# memorycard.net
KiCad netlist of a schematic drawn in Altium Designer
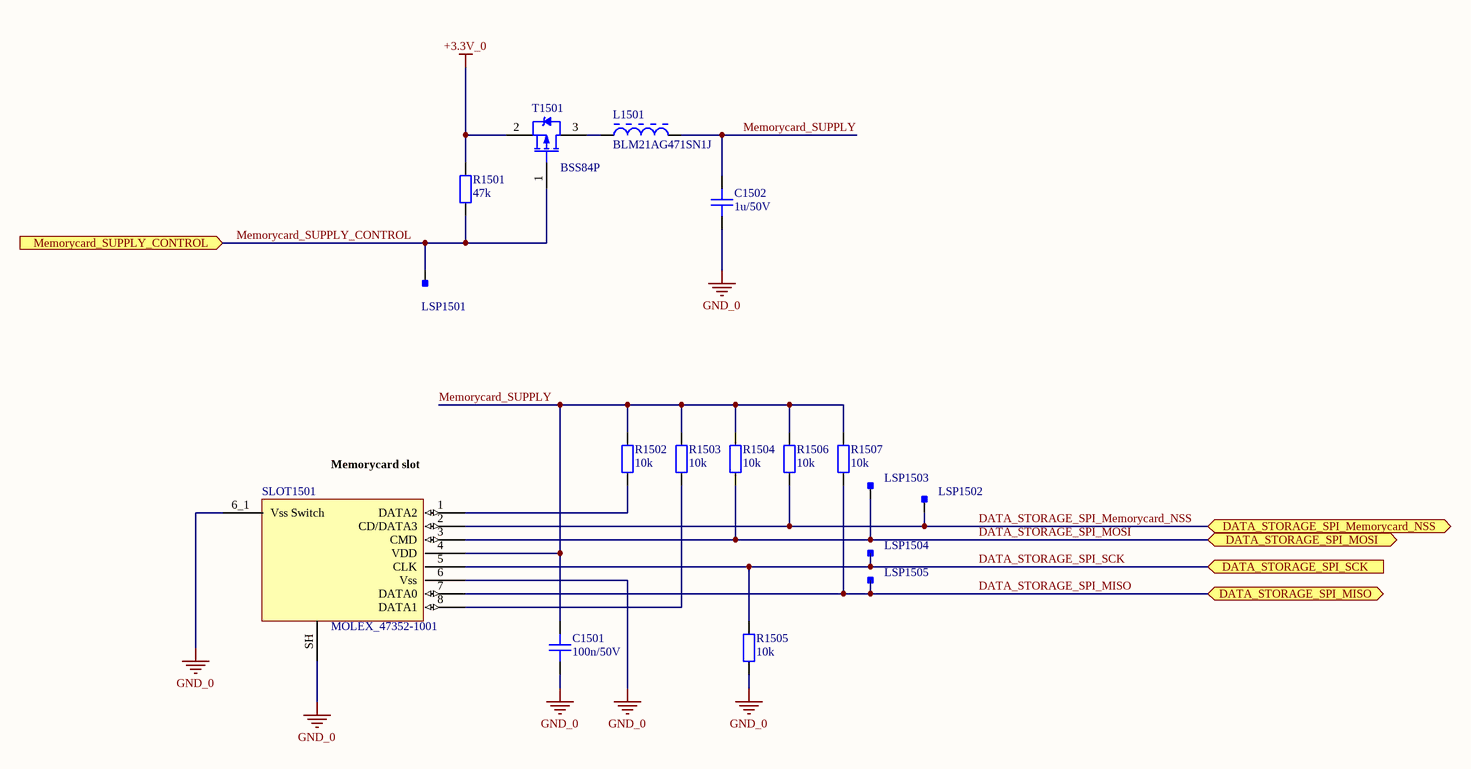
[diagram p0: memorycard.SchDoc]

(export (version "E")
  (design (tool "Eeschema 10.0.6"))
  (components
    (comp (ref "C1501")
      (value "100n/50V")
      (footprint "CAPC1608X08N")
      (description "MLCC")
      (fields (field (name "PART NUMBER") "gen_C_ceramic_100n_50V_X7R_0603"))
      (libsource (lib "OE750") (part "C"))
    )
    (comp (ref "C1502")
      (value "1u/50V")
      (footprint "CAPC1608X08N")
      (description "MLCC")
      (fields (field (name "PART NUMBER") "gen_C_ceramic_1u_50V_X7R_0603") (field (name "TOLERANCE") "± 10%"))
      (libsource (lib "OE750") (part "C"))
    )
    (comp (ref "L1501")
      (value "BLM21AG471SN1J")
      (footprint "MURA-BLM21-H1-CHIP-2_V")
      (fields (field (name "MANUFACTURER") "Murata"))
      (libsource (lib "Altium Content Vault") (part "MURA-FB-2"))
    )
    (comp (ref "LSP1501")
      (value "Testpoint_Square")
      (footprint "Testpoint_S1")
      (description "Testpoint, square")
      (libsource (lib "OE750") (part "Testpoint_Square"))
    )
    (comp (ref "LSP1502")
      (value "Testpoint_Square")
      (footprint "Testpoint_S1")
      (description "Testpoint, square")
      (libsource (lib "OE750") (part "Testpoint_Square"))
    )
    (comp (ref "LSP1503")
      (value "Testpoint_Square")
      (footprint "Testpoint_S1")
      (description "Testpoint, square")
      (libsource (lib "OE750") (part "Testpoint_Square"))
    )
    (comp (ref "LSP1504")
      (value "Testpoint_Square")
      (footprint "Testpoint_S1")
      (description "Testpoint, square")
      (libsource (lib "OE750") (part "Testpoint_Square"))
    )
    (comp (ref "LSP1505")
      (value "Testpoint_Square")
      (footprint "Testpoint_S1")
      (description "Testpoint, square")
      (libsource (lib "OE750") (part "Testpoint_Square"))
    )
    (comp (ref "R1501")
      (value "47k")
      (footprint "RESC1608X05N")
      (description "SMD Resistor 47k 0603")
      (fields (field (name "PART NUMBER") "gen_R_47k_0603") (field (name "TOLERANCE") "1%"))
      (libsource (lib "OE750") (part "R"))
    )
    (comp (ref "R1502")
      (value "10k")
      (footprint "RESC1608X05N")
      (description "SMD Resistor 10k 0603")
      (fields (field (name "PART NUMBER") "gen_R_10k_0603") (field (name "TOLERANCE") "1%"))
      (libsource (lib "OE750") (part "R"))
    )
    (comp (ref "R1503")
      (value "10k")
      (footprint "RESC1608X05N")
      (description "SMD Resistor 10k 0603")
      (fields (field (name "PART NUMBER") "gen_R_10k_0603") (field (name "TOLERANCE") "1%"))
      (libsource (lib "OE750") (part "R"))
    )
    (comp (ref "R1504")
      (value "10k")
      (footprint "RESC1608X05N")
      (description "SMD Resistor 10k 0603")
      (fields (field (name "PART NUMBER") "gen_R_10k_0603") (field (name "TOLERANCE") "1%"))
      (libsource (lib "OE750") (part "R"))
    )
    (comp (ref "R1505")
      (value "10k")
      (footprint "RESC1608X05N")
      (description "SMD Resistor 10k 0603")
      (fields (field (name "PART NUMBER") "gen_R_10k_0603") (field (name "TOLERANCE") "1%"))
      (libsource (lib "OE750") (part "R"))
    )
    (comp (ref "R1506")
      (value "10k")
      (footprint "RESC1608X05N")
      (description "SMD Resistor 10k 0603")
      (fields (field (name "PART NUMBER") "gen_R_10k_0603") (field (name "TOLERANCE") "1%"))
      (libsource (lib "OE750") (part "R"))
    )
    (comp (ref "R1507")
      (value "10k")
      (footprint "RESC1608X05N")
      (description "SMD Resistor 10k 0603")
      (fields (field (name "PART NUMBER") "gen_R_10k_0603") (field (name "TOLERANCE") "1%"))
      (libsource (lib "OE750") (part "R"))
    )
    (comp (ref "SLOT1501")
      (value "MOLEX_47352-1001")
      (footprint "MOLEX_47352_1001")
      (fields (field (name "PART NUMBER") "molex_47352-1001") (field (name "MANUFACTURER") "Molex"))
      (libsource (lib "OE750") (part "MOLEX_47352-1001"))
    )
    (comp (ref "T1501")
      (value "BSS84P")
      (footprint "INF-PG-SOT23_N")
      (fields (field (name "MANUFACTURER") "Infineon"))
      (libsource (lib "Altium Content Vault") (part "INF-PEMOS-GSD-3-B"))
    )
  )
  (nets
    (net (code "1") (name "+3.3V_0") (class "Default")
      (node (ref "R1501") (pin "2") (pinfunction "2_2") (pintype "passive"))
      (node (ref "T1501") (pin "2") (pinfunction "SOURCE_2") (pintype "passive"))
    )
    (net (code "2") (name "/DATA_STORAGE_SPI_MISO") (class "Default")
      (node (ref "LSP1505") (pin "1") (pinfunction "1_1") (pintype "passive"))
      (node (ref "R1507") (pin "1") (pinfunction "1_1") (pintype "passive"))
      (node (ref "SLOT1501") (pin "7") (pinfunction "DATA0_7") (pintype "bidirectional"))
    )
    (net (code "3") (name "/DATA_STORAGE_SPI_MOSI") (class "Default")
      (node (ref "LSP1503") (pin "1") (pinfunction "1_1") (pintype "passive"))
      (node (ref "R1504") (pin "1") (pinfunction "1_1") (pintype "passive"))
      (node (ref "SLOT1501") (pin "3") (pinfunction "CMD_3") (pintype "bidirectional"))
    )
    (net (code "4") (name "/DATA_STORAGE_SPI_Memorycard_NSS") (class "Default")
      (node (ref "LSP1502") (pin "1") (pinfunction "1_1") (pintype "passive"))
      (node (ref "R1506") (pin "1") (pinfunction "1_1") (pintype "passive"))
      (node (ref "SLOT1501") (pin "2") (pinfunction "CD/DATA3_2") (pintype "bidirectional"))
    )
    (net (code "5") (name "/DATA_STORAGE_SPI_SCK") (class "Default")
      (node (ref "LSP1504") (pin "1") (pinfunction "1_1") (pintype "passive"))
      (node (ref "R1505") (pin "2") (pinfunction "2_2") (pintype "passive"))
      (node (ref "SLOT1501") (pin "5") (pinfunction "CLK_5") (pintype "passive"))
    )
    (net (code "6") (name "/Memorycard_SUPPLY") (class "Default")
      (node (ref "C1501") (pin "2") (pinfunction "2_2") (pintype "passive"))
      (node (ref "C1502") (pin "1") (pinfunction "1_1") (pintype "passive"))
      (node (ref "L1501") (pin "1") (pinfunction "1_1") (pintype "passive"))
      (node (ref "R1502") (pin "2") (pinfunction "2_2") (pintype "passive"))
      (node (ref "R1503") (pin "2") (pinfunction "2_2") (pintype "passive"))
      (node (ref "R1504") (pin "2") (pinfunction "2_2") (pintype "passive"))
      (node (ref "R1506") (pin "2") (pinfunction "2_2") (pintype "passive"))
      (node (ref "R1507") (pin "2") (pinfunction "2_2") (pintype "passive"))
      (node (ref "SLOT1501") (pin "4") (pinfunction "VDD_4") (pintype "power_in"))
    )
    (net (code "7") (name "/Memorycard_SUPPLY_CONTROL") (class "Default")
      (node (ref "LSP1501") (pin "1") (pinfunction "1_1") (pintype "passive"))
      (node (ref "R1501") (pin "1") (pinfunction "1_1") (pintype "passive"))
      (node (ref "T1501") (pin "1") (pinfunction "GATE_1") (pintype "passive"))
    )
    (net (code "8") (name "GND_0") (class "Default")
      (node (ref "C1501") (pin "1") (pinfunction "1_1") (pintype "passive"))
      (node (ref "C1502") (pin "2") (pinfunction "2_2") (pintype "passive"))
      (node (ref "R1505") (pin "1") (pinfunction "1_1") (pintype "passive"))
      (node (ref "SLOT1501") (pin "6") (pinfunction "Vss_6") (pintype "power_in"))
      (node (ref "SLOT1501") (pin "6_1") (pinfunction "Vss_Switch_6_1") (pintype "passive"))
      (node (ref "SLOT1501") (pin "SH") (pintype "passive"))
    )
    (net (code "9") (name "Net-(SLOT1501-DATA1)") (class "Default")
      (node (ref "R1503") (pin "1") (pinfunction "1_1") (pintype "passive"))
      (node (ref "SLOT1501") (pin "8") (pinfunction "DATA1_8") (pintype "bidirectional"))
    )
    (net (code "10") (name "Net-(SLOT1501-DATA2)") (class "Default")
      (node (ref "R1502") (pin "1") (pinfunction "1_1") (pintype "passive"))
      (node (ref "SLOT1501") (pin "1") (pinfunction "DATA2_1") (pintype "bidirectional"))
    )
    (net (code "11") (name "Net-(T1501-DRAIN)") (class "Default")
      (node (ref "L1501") (pin "2") (pinfunction "2_2") (pintype "passive"))
      (node (ref "T1501") (pin "3") (pinfunction "DRAIN_3") (pintype "passive"))
    )
  )
)
